# SCH_STM32__2024-11-28.net
KiCad netlist of a schematic drawn in EasyEDA
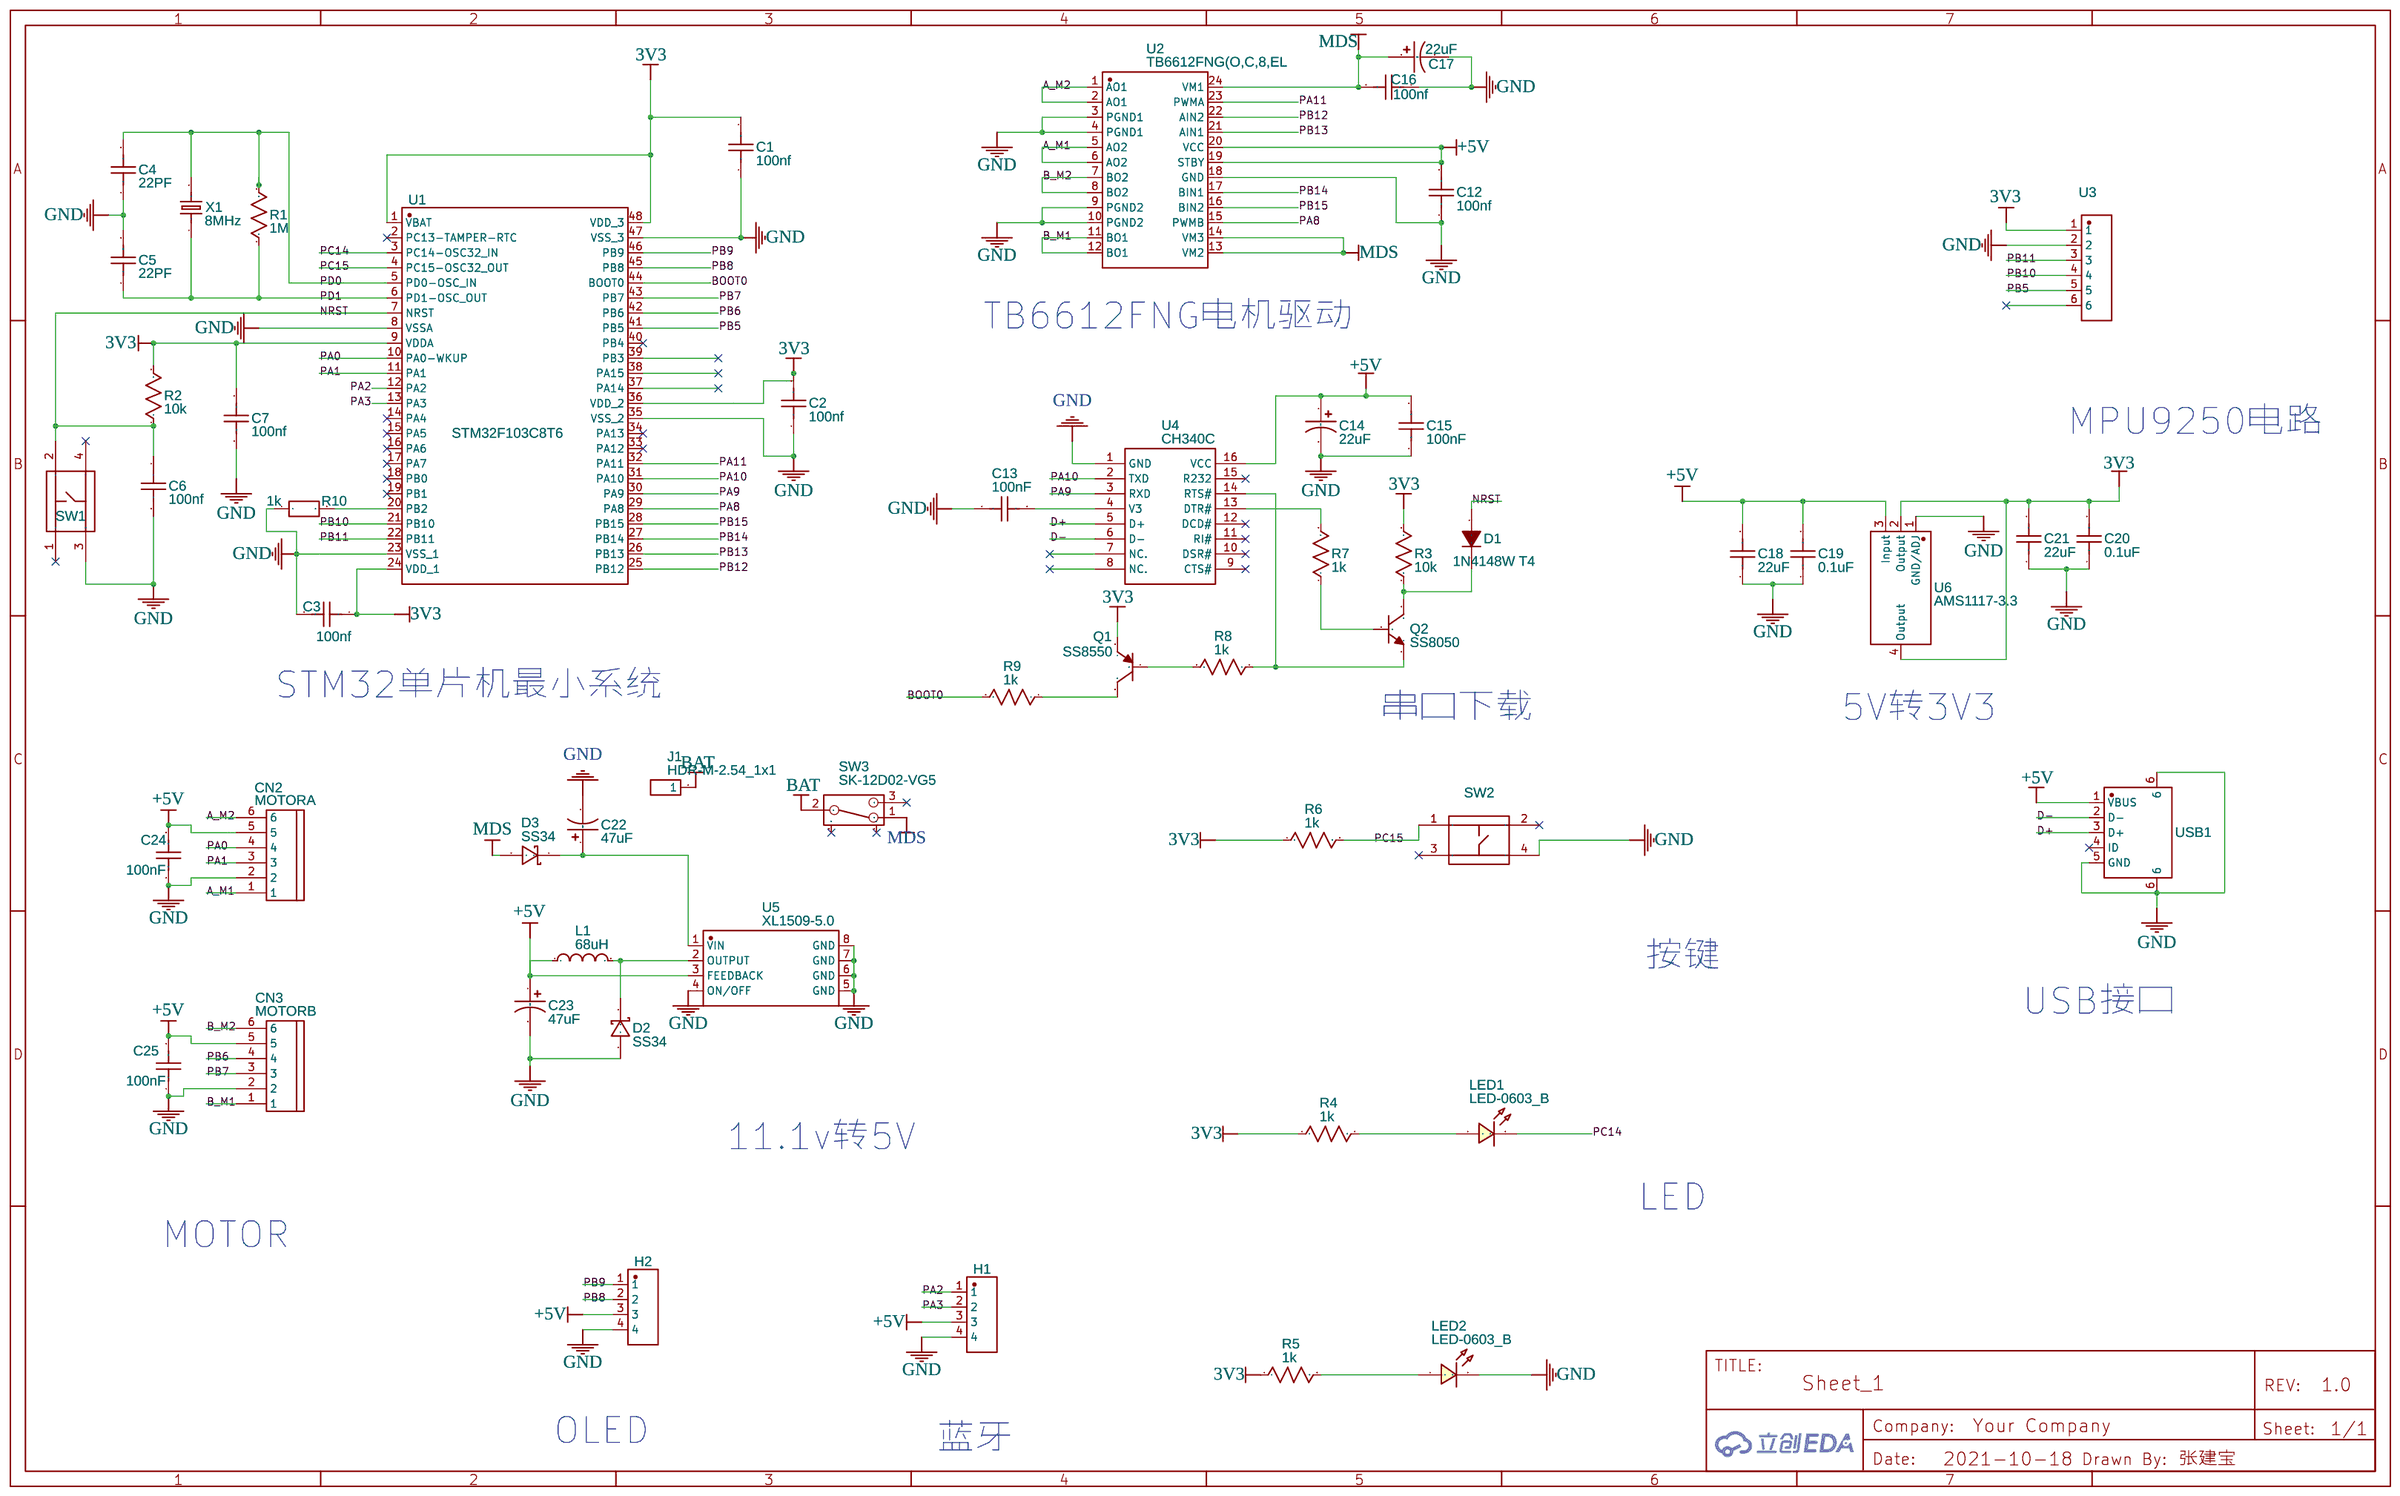
[diagram p0: schematic sheet]

(export (version "E")
  (design (tool "Eeschema 10.0.6"))
  (components
    (comp (ref "C1") (value "100nf") (libsource (lib "") (part "C_0805_US")))
    (comp (ref "C2") (value "100nf") (libsource (lib "") (part "C_0805_US")))
    (comp (ref "C3") (value "100nf") (libsource (lib "") (part "C_0805_US_1")))
    (comp (ref "C4") (value "22PF") (libsource (lib "") (part "C_0603_US")))
    (comp (ref "C5") (value "22PF") (libsource (lib "") (part "C_0603_US")))
    (comp (ref "C6") (value "100nf") (libsource (lib "") (part "C_0805_US_3")))
    (comp (ref "C7") (value "100nf") (libsource (lib "") (part "C_0805_US_3")))
    (comp (ref "C12") (value "100nf") (libsource (lib "") (part "C_0805_US")))
    (comp (ref "C13") (value "100nF") (libsource (lib "") (part "C_0805_US_2")))
    (comp (ref "C14") (value "22uF") (libsource (lib "") (part "C_Tan_SMD_A_US_3")))
    (comp (ref "C15") (value "100nF") (libsource (lib "") (part "C_0805_US")))
    (comp (ref "C16") (value "100nf") (libsource (lib "") (part "C_0805_US_1")))
    (comp (ref "C17") (value "22uF") (libsource (lib "") (part "C_Tan_SMD_A_US_2")))
    (comp (ref "C18") (value "22uF") (libsource (lib "") (part "C_0805_US")))
    (comp (ref "C19") (value "0.1uF") (libsource (lib "") (part "C_0805_US")))
    (comp (ref "C20") (value "0.1uF") (libsource (lib "") (part "C_0805_US")))
    (comp (ref "C21") (value "22uF") (libsource (lib "") (part "C_0805_US")))
    (comp (ref "C22") (value "47uF") (libsource (lib "") (part "C_Tan_SMD_A_US_1")))
    (comp (ref "C23") (value "47uF") (libsource (lib "") (part "C_Tan_SMD_A_US")))
    (comp (ref "C24") (value "100nF") (libsource (lib "") (part "C_0805_US")))
    (comp (ref "C25") (value "100nF") (libsource (lib "") (part "C_0805_US")))
    (comp (ref "CN2")
      (value "MOTORA")
      (fields (field (name "Manufacturer Part") "XH-6AW") (field (name "Manufacturer") "BOOMELE"))
      (libsource (lib "") (part "XH-6AW_C8876"))
    )
    (comp (ref "CN3")
      (value "MOTORB")
      (fields (field (name "Manufacturer Part") "XH-6AW") (field (name "Manufacturer") "BOOMELE"))
      (libsource (lib "") (part "XH-6AW_C8876"))
    )
    (comp (ref "D1")
      (value "1N4148W T4")
      (fields (field (name "Manufacturer") "CJ"))
      (libsource (lib "") (part "1N4148W T4"))
    )
    (comp (ref "D2")
      (value "SS34")
      (fields (field (name "Manufacturer") "High Diode"))
      (libsource (lib "") (part "SS34_C466502_1"))
    )
    (comp (ref "D3")
      (value "SS34")
      (fields (field (name "Manufacturer") "High Diode"))
      (libsource (lib "") (part "SS34_C466502"))
    )
    (comp (ref "H1")
      (value "2.54-1*4P母")
      (fields (field (name "Manufacturer") "BOOMELE(博穆精密)"))
      (libsource (lib "") (part "2.54-1*4P母"))
    )
    (comp (ref "H2")
      (value "2.54-1*4P母")
      (fields (field (name "Manufacturer") "BOOMELE(博穆精密)"))
      (libsource (lib "") (part "2.54-1*4P母"))
    )
    (comp (ref "J1") (value "HDR-M-2.54_1x1") (libsource (lib "") (part "HDR-M-2.54_1x1")))
    (comp (ref "L1")
      (value "68uH")
      (fields
        (field (name "Manufacturer Part") "SLH1207S680MTT")
        (field (name "Manufacturer") "Sunltech Tech")
      )
      (libsource (lib "") (part "SLH1207S680MTT"))
    )
    (comp (ref "LED1")
      (value "LED-0603_B")
      (fields
        (field (name "Manufacturer Part") "19-217/BHC-ZL1M2RY/3T")
        (field (name "Manufacturer") "EVERLIGHT(台湾亿光)")
      )
      (libsource (lib "") (part "LED-0603_B"))
    )
    (comp (ref "LED2")
      (value "LED-0603_B")
      (fields
        (field (name "Manufacturer Part") "19-217/BHC-ZL1M2RY/3T")
        (field (name "Manufacturer") "EVERLIGHT(台湾亿光)")
      )
      (libsource (lib "") (part "LED-0603_B"))
    )
    (comp (ref "Q1")
      (value "SS8550")
      (fields (field (name "Manufacturer") "晶导微电子"))
      (libsource (lib "") (part "SS8550_C2762207"))
    )
    (comp (ref "Q2")
      (value "SS8050")
      (fields (field (name "Manufacturer") "AnBon"))
      (libsource (lib "") (part "SS8050_C541705"))
    )
    (comp (ref "R1") (value "1M") (libsource (lib "") (part "R_0805_US_2")))
    (comp (ref "R2") (value "10k") (libsource (lib "") (part "R_0805_US_2")))
    (comp (ref "R3") (value "10k") (libsource (lib "") (part "R_0805_US_2")))
    (comp (ref "R4") (value "1k") (libsource (lib "") (part "R_0805_US")))
    (comp (ref "R5") (value "1k") (libsource (lib "") (part "R_0805_US")))
    (comp (ref "R6") (value "1k") (libsource (lib "") (part "R_0805_US")))
    (comp (ref "R7") (value "1k") (libsource (lib "") (part "R_0805_US_2")))
    (comp (ref "R8") (value "1k") (libsource (lib "") (part "R_0805_US_1")))
    (comp (ref "R9") (value "1k") (libsource (lib "") (part "R_0805_US_1")))
    (comp (ref "R10") (value "1k") (libsource (lib "") (part "R_0603_EU")))
    (comp (ref "SW1")
      (value "K2-1102DP-C4SW-04")
      (fields (field (name "Manufacturer") "HRO"))
      (libsource (lib "") (part "K2-1102DP-C4SW-04"))
    )
    (comp (ref "SW2")
      (value "K2-1102DP-C4SW-04")
      (fields (field (name "Manufacturer") "HRO"))
      (libsource (lib "") (part "K2-1102DP-C4SW-04_1"))
    )
    (comp (ref "SW3")
      (value "SK-12D02-VG5")
      (fields (field (name "Manufacturer") "Rectangular Connectors - Contacts"))
      (libsource (lib "") (part "SK-12D02-VG5"))
    )
    (comp (ref "U1")
      (value "STM32F103C8T6")
      (fields (field (name "Manufacturer") "STMicroelectronics"))
      (libsource (lib "") (part "STM32F103C8T6"))
    )
    (comp (ref "U2")
      (value "TB6612FNG(O,C,8,EL")
      (fields (field (name "Manufacturer") "TOSHIBA"))
      (libsource (lib "") (part "TB6612FNG(O,C,8,EL"))
    )
    (comp (ref "U3")
      (value "A2541HWV-6P_C2897443")
      (fields (field (name "Manufacturer Part") "A2541HWV-6P") (field (name "Manufacturer") "CJT(长江连接器)"))
      (libsource (lib "") (part "A2541HWV-6P_C2897443"))
    )
    (comp (ref "U4")
      (value "CH340C")
      (fields (field (name "Manufacturer") "WCH"))
      (libsource (lib "") (part "CH340C"))
    )
    (comp (ref "U5")
      (value "XL1509-5.0")
      (fields (field (name "Manufacturer") "UMW(友台半导体)"))
      (libsource (lib "") (part "XL1509-5.0_C2902368"))
    )
    (comp (ref "U6")
      (value "AMS1117-3.3")
      (fields (field (name "Manufacturer") "KEXIN"))
      (libsource (lib "") (part "AMS1117-3.3_C369933"))
    )
    (comp (ref "USB1")
      (value "U-M-M5DS-W-5_C2689963")
      (fields (field (name "Manufacturer Part") "U-M-M5DS-W-5") (field (name "Manufacturer") "韩国韩荣"))
      (libsource (lib "") (part "U-M-M5DS-W-5_C2689963"))
    )
    (comp (ref "X1")
      (value "8MHz")
      (fields
        (field (name "Manufacturer Part") "49S-8.000-20-20-20/A")
        (field (name "Manufacturer") "Suzhou Liming Elec")
      )
      (libsource (lib "") (part "49S-8.000-20-20-20/A"))
    )
  )
  (nets
    (net (code "1") (name "+5V") (class "Default")
      (node (ref "C12") (pin "2") (pinfunction "2_2") (pintype "unspecified"))
      (node (ref "C14") (pin "1") (pinfunction "1_1") (pintype "unspecified"))
      (node (ref "C15") (pin "2") (pinfunction "2_2") (pintype "unspecified"))
      (node (ref "C18") (pin "2") (pinfunction "2_2") (pintype "unspecified"))
      (node (ref "C19") (pin "2") (pinfunction "2_2") (pintype "unspecified"))
      (node (ref "C23") (pin "1") (pinfunction "1_1") (pintype "unspecified"))
      (node (ref "C24") (pin "2") (pinfunction "2_2") (pintype "unspecified"))
      (node (ref "C25") (pin "2") (pinfunction "2_2") (pintype "unspecified"))
      (node (ref "CN2") (pin "5") (pinfunction "5_5") (pintype "unspecified"))
      (node (ref "CN3") (pin "5") (pinfunction "5_5") (pintype "unspecified"))
      (node (ref "H1") (pin "3") (pinfunction "3_3") (pintype "unspecified"))
      (node (ref "H2") (pin "3") (pinfunction "3_3") (pintype "unspecified"))
      (node (ref "L1") (pin "1") (pinfunction "1_1") (pintype "unspecified"))
      (node (ref "U2") (pin "19") (pinfunction "STBY_19") (pintype "unspecified"))
      (node (ref "U2") (pin "20") (pinfunction "VCC_20") (pintype "unspecified"))
      (node (ref "U4") (pin "16") (pinfunction "VCC_16") (pintype "unspecified"))
      (node (ref "U5") (pin "3") (pinfunction "FEEDBACK_3") (pintype "unspecified"))
      (node (ref "U6") (pin "3") (pinfunction "Input_3") (pintype "unspecified"))
      (node (ref "USB1") (pin "1") (pinfunction "VBUS_1") (pintype "unspecified"))
    )
    (net (code "2") (name "/A_M1") (class "Default")
      (node (ref "CN2") (pin "1") (pinfunction "1_1") (pintype "unspecified"))
      (node (ref "U2") (pin "5") (pinfunction "AO2_5") (pintype "unspecified"))
      (node (ref "U2") (pin "6") (pinfunction "AO2_6") (pintype "unspecified"))
    )
    (net (code "3") (name "/A_M2") (class "Default")
      (node (ref "CN2") (pin "6") (pinfunction "6_6") (pintype "unspecified"))
      (node (ref "U2") (pin "1") (pinfunction "AO1_1") (pintype "unspecified"))
      (node (ref "U2") (pin "2") (pinfunction "AO1_2") (pintype "unspecified"))
    )
    (net (code "4") (name "/BOOT0") (class "Default")
      (node (ref "R9") (pin "2") (pinfunction "2_2") (pintype "unspecified"))
      (node (ref "U1") (pin "44") (pinfunction "BOOT0_44") (pintype "unspecified"))
    )
    (net (code "5") (name "/B_M1") (class "Default")
      (node (ref "CN3") (pin "1") (pinfunction "1_1") (pintype "unspecified"))
      (node (ref "U2") (pin "11") (pinfunction "BO1_11") (pintype "unspecified"))
      (node (ref "U2") (pin "12") (pinfunction "BO1_12") (pintype "unspecified"))
    )
    (net (code "6") (name "/B_M2") (class "Default")
      (node (ref "CN3") (pin "6") (pinfunction "6_6") (pintype "unspecified"))
      (node (ref "U2") (pin "7") (pinfunction "BO2_7") (pintype "unspecified"))
      (node (ref "U2") (pin "8") (pinfunction "BO2_8") (pintype "unspecified"))
    )
    (net (code "7") (name "/D+") (class "Default")
      (node (ref "U4") (pin "5") (pinfunction "D+_5") (pintype "unspecified"))
      (node (ref "USB1") (pin "3") (pinfunction "D+_3") (pintype "unspecified"))
    )
    (net (code "8") (name "/D-") (class "Default")
      (node (ref "U4") (pin "6") (pinfunction "D-_6") (pintype "unspecified"))
      (node (ref "USB1") (pin "2") (pinfunction "D-_2") (pintype "unspecified"))
    )
    (net (code "9") (name "/NRST") (class "Default")
      (node (ref "C6") (pin "1") (pinfunction "1_1") (pintype "unspecified"))
      (node (ref "D1") (pin "2") (pinfunction "A_2") (pintype "unspecified"))
      (node (ref "R2") (pin "1") (pinfunction "1_1") (pintype "unspecified"))
      (node (ref "SW1") (pin "2") (pinfunction "2_2") (pintype "unspecified"))
      (node (ref "U1") (pin "7") (pinfunction "NRST_7") (pintype "unspecified"))
    )
    (net (code "10") (name "/PA0") (class "Default")
      (node (ref "CN2") (pin "4") (pinfunction "4_4") (pintype "unspecified"))
      (node (ref "U1") (pin "10") (pinfunction "PA0-WKUP_10") (pintype "unspecified"))
    )
    (net (code "11") (name "/PA1") (class "Default")
      (node (ref "CN2") (pin "3") (pinfunction "3_3") (pintype "unspecified"))
      (node (ref "U1") (pin "11") (pinfunction "PA1_11") (pintype "unspecified"))
    )
    (net (code "12") (name "/PA2") (class "Default")
      (node (ref "H1") (pin "1") (pinfunction "1_1") (pintype "unspecified"))
      (node (ref "U1") (pin "12") (pinfunction "PA2_12") (pintype "unspecified"))
    )
    (net (code "13") (name "/PA3") (class "Default")
      (node (ref "H1") (pin "2") (pinfunction "2_2") (pintype "unspecified"))
      (node (ref "U1") (pin "13") (pinfunction "PA3_13") (pintype "unspecified"))
    )
    (net (code "14") (name "/PA8") (class "Default")
      (node (ref "U1") (pin "29") (pinfunction "PA8_29") (pintype "unspecified"))
      (node (ref "U2") (pin "15") (pinfunction "PWMB_15") (pintype "unspecified"))
    )
    (net (code "15") (name "/PA9") (class "Default")
      (node (ref "U1") (pin "30") (pinfunction "PA9_30") (pintype "unspecified"))
      (node (ref "U4") (pin "3") (pinfunction "RXD_3") (pintype "unspecified"))
    )
    (net (code "16") (name "/PA10") (class "Default")
      (node (ref "U1") (pin "31") (pinfunction "PA10_31") (pintype "unspecified"))
      (node (ref "U4") (pin "2") (pinfunction "TXD_2") (pintype "unspecified"))
    )
    (net (code "17") (name "/PA11") (class "Default")
      (node (ref "U1") (pin "32") (pinfunction "PA11_32") (pintype "unspecified"))
      (node (ref "U2") (pin "23") (pinfunction "PWMA_23") (pintype "unspecified"))
    )
    (net (code "18") (name "/PB5") (class "Default")
      (node (ref "U1") (pin "41") (pinfunction "PB5_41") (pintype "unspecified"))
      (node (ref "U3") (pin "5") (pinfunction "5_5") (pintype "unspecified"))
    )
    (net (code "19") (name "/PB6") (class "Default")
      (node (ref "CN3") (pin "4") (pinfunction "4_4") (pintype "unspecified"))
      (node (ref "U1") (pin "42") (pinfunction "PB6_42") (pintype "unspecified"))
    )
    (net (code "20") (name "/PB7") (class "Default")
      (node (ref "CN3") (pin "3") (pinfunction "3_3") (pintype "unspecified"))
      (node (ref "U1") (pin "43") (pinfunction "PB7_43") (pintype "unspecified"))
    )
    (net (code "21") (name "/PB8") (class "Default")
      (node (ref "H2") (pin "2") (pinfunction "2_2") (pintype "unspecified"))
      (node (ref "U1") (pin "45") (pinfunction "PB8_45") (pintype "unspecified"))
    )
    (net (code "22") (name "/PB9") (class "Default")
      (node (ref "H2") (pin "1") (pinfunction "1_1") (pintype "unspecified"))
      (node (ref "U1") (pin "46") (pinfunction "PB9_46") (pintype "unspecified"))
    )
    (net (code "23") (name "/PB10") (class "Default")
      (node (ref "U1") (pin "21") (pinfunction "PB10_21") (pintype "unspecified"))
      (node (ref "U3") (pin "4") (pinfunction "4_4") (pintype "unspecified"))
    )
    (net (code "24") (name "/PB11") (class "Default")
      (node (ref "U1") (pin "22") (pinfunction "PB11_22") (pintype "unspecified"))
      (node (ref "U3") (pin "3") (pinfunction "3_3") (pintype "unspecified"))
    )
    (net (code "25") (name "/PB12") (class "Default")
      (node (ref "U1") (pin "25") (pinfunction "PB12_25") (pintype "unspecified"))
      (node (ref "U2") (pin "22") (pinfunction "AIN2_22") (pintype "unspecified"))
    )
    (net (code "26") (name "/PB13") (class "Default")
      (node (ref "U1") (pin "26") (pinfunction "PB13_26") (pintype "unspecified"))
      (node (ref "U2") (pin "21") (pinfunction "AIN1_21") (pintype "unspecified"))
    )
    (net (code "27") (name "/PB14") (class "Default")
      (node (ref "U1") (pin "27") (pinfunction "PB14_27") (pintype "unspecified"))
      (node (ref "U2") (pin "17") (pinfunction "BIN1_17") (pintype "unspecified"))
    )
    (net (code "28") (name "/PB15") (class "Default")
      (node (ref "U1") (pin "28") (pinfunction "PB15_28") (pintype "unspecified"))
      (node (ref "U2") (pin "16") (pinfunction "BIN2_16") (pintype "unspecified"))
    )
    (net (code "29") (name "/PC14") (class "Default")
      (node (ref "LED1") (pin "2") (pinfunction "2_2") (pintype "unspecified"))
      (node (ref "U1") (pin "3") (pinfunction "PC14-OSC32_IN_3") (pintype "unspecified"))
    )
    (net (code "30") (name "/PC15") (class "Default")
      (node (ref "R6") (pin "2") (pinfunction "2_2") (pintype "unspecified"))
      (node (ref "SW2") (pin "1") (pinfunction "1_1") (pintype "unspecified"))
      (node (ref "U1") (pin "4") (pinfunction "PC15-OSC32_OUT_4") (pintype "unspecified"))
    )
    (net (code "31") (name "/PD0") (class "Default")
      (node (ref "C4") (pin "2") (pinfunction "2_2") (pintype "unspecified"))
      (node (ref "R1") (pin "2") (pinfunction "2_2") (pintype "unspecified"))
      (node (ref "U1") (pin "5") (pinfunction "PD0-OSC_IN_5") (pintype "unspecified"))
      (node (ref "X1") (pin "2") (pinfunction "2_2") (pintype "unspecified"))
    )
    (net (code "32") (name "/PD1") (class "Default")
      (node (ref "C5") (pin "1") (pinfunction "1_1") (pintype "unspecified"))
      (node (ref "R1") (pin "1") (pinfunction "1_1") (pintype "unspecified"))
      (node (ref "U1") (pin "6") (pinfunction "PD1-OSC_OUT_6") (pintype "unspecified"))
      (node (ref "X1") (pin "1") (pinfunction "1_1") (pintype "unspecified"))
    )
    (net (code "33") (name "3V3") (class "Default")
      (node (ref "C1") (pin "2") (pinfunction "2_2") (pintype "unspecified"))
      (node (ref "C2") (pin "2") (pinfunction "2_2") (pintype "unspecified"))
      (node (ref "C20") (pin "2") (pinfunction "2_2") (pintype "unspecified"))
      (node (ref "C21") (pin "2") (pinfunction "2_2") (pintype "unspecified"))
      (node (ref "C3") (pin "1") (pinfunction "1_1") (pintype "unspecified"))
      (node (ref "C7") (pin "1") (pinfunction "1_1") (pintype "unspecified"))
      (node (ref "Q1") (pin "2") (pinfunction "E_2") (pintype "unspecified"))
      (node (ref "R2") (pin "2") (pinfunction "2_2") (pintype "unspecified"))
      (node (ref "R3") (pin "2") (pinfunction "2_2") (pintype "unspecified"))
      (node (ref "R4") (pin "1") (pinfunction "1_1") (pintype "unspecified"))
      (node (ref "R5") (pin "1") (pinfunction "1_1") (pintype "unspecified"))
      (node (ref "R6") (pin "1") (pinfunction "1_1") (pintype "unspecified"))
      (node (ref "U1") (pin "1") (pinfunction "VBAT_1") (pintype "unspecified"))
      (node (ref "U1") (pin "24") (pinfunction "VDD_1_24") (pintype "unspecified"))
      (node (ref "U1") (pin "36") (pinfunction "VDD_2_36") (pintype "unspecified"))
      (node (ref "U1") (pin "48") (pinfunction "VDD_3_48") (pintype "unspecified"))
      (node (ref "U1") (pin "9") (pinfunction "VDDA_9") (pintype "unspecified"))
      (node (ref "U3") (pin "1") (pinfunction "1_1") (pintype "unspecified"))
      (node (ref "U6") (pin "2") (pinfunction "Output_2") (pintype "unspecified"))
      (node (ref "U6") (pin "4") (pinfunction "Output_4") (pintype "unspecified"))
    )
    (net (code "34") (name "BAT") (class "Default")
      (node (ref "J1") (pin "1") (pinfunction "1_1") (pintype "input"))
      (node (ref "SW3") (pin "2") (pinfunction "2_2") (pintype "unspecified"))
    )
    (net (code "35") (name "GND") (class "Default")
      (node (ref "C1") (pin "1") (pinfunction "1_1") (pintype "unspecified"))
      (node (ref "C12") (pin "1") (pinfunction "1_1") (pintype "unspecified"))
      (node (ref "C13") (pin "1") (pinfunction "1_1") (pintype "unspecified"))
      (node (ref "C14") (pin "2") (pinfunction "2_2") (pintype "unspecified"))
      (node (ref "C15") (pin "1") (pinfunction "1_1") (pintype "unspecified"))
      (node (ref "C16") (pin "1") (pinfunction "1_1") (pintype "unspecified"))
      (node (ref "C17") (pin "2") (pinfunction "2_2") (pintype "unspecified"))
      (node (ref "C18") (pin "1") (pinfunction "1_1") (pintype "unspecified"))
      (node (ref "C19") (pin "1") (pinfunction "1_1") (pintype "unspecified"))
      (node (ref "C2") (pin "1") (pinfunction "1_1") (pintype "unspecified"))
      (node (ref "C20") (pin "1") (pinfunction "1_1") (pintype "unspecified"))
      (node (ref "C21") (pin "1") (pinfunction "1_1") (pintype "unspecified"))
      (node (ref "C22") (pin "2") (pinfunction "2_2") (pintype "unspecified"))
      (node (ref "C23") (pin "2") (pinfunction "2_2") (pintype "unspecified"))
      (node (ref "C24") (pin "1") (pinfunction "1_1") (pintype "unspecified"))
      (node (ref "C25") (pin "1") (pinfunction "1_1") (pintype "unspecified"))
      (node (ref "C3") (pin "2") (pinfunction "2_2") (pintype "unspecified"))
      (node (ref "C4") (pin "1") (pinfunction "1_1") (pintype "unspecified"))
      (node (ref "C5") (pin "2") (pinfunction "2_2") (pintype "unspecified"))
      (node (ref "C6") (pin "2") (pinfunction "2_2") (pintype "unspecified"))
      (node (ref "C7") (pin "2") (pinfunction "2_2") (pintype "unspecified"))
      (node (ref "CN2") (pin "2") (pinfunction "2_2") (pintype "unspecified"))
      (node (ref "CN3") (pin "2") (pinfunction "2_2") (pintype "unspecified"))
      (node (ref "D2") (pin "2") (pinfunction "2_2") (pintype "unspecified"))
      (node (ref "H1") (pin "4") (pinfunction "4_4") (pintype "unspecified"))
      (node (ref "H2") (pin "4") (pinfunction "4_4") (pintype "unspecified"))
      (node (ref "LED2") (pin "2") (pinfunction "2_2") (pintype "unspecified"))
      (node (ref "R10") (pin "1") (pinfunction "1_1") (pintype "unspecified"))
      (node (ref "SW1") (pin "3") (pinfunction "3_3") (pintype "unspecified"))
      (node (ref "SW2") (pin "4") (pinfunction "4_4") (pintype "unspecified"))
      (node (ref "U1") (pin "23") (pinfunction "VSS_1_23") (pintype "unspecified"))
      (node (ref "U1") (pin "35") (pinfunction "VSS_2_35") (pintype "unspecified"))
      (node (ref "U1") (pin "47") (pinfunction "VSS_3_47") (pintype "unspecified"))
      (node (ref "U1") (pin "8") (pinfunction "VSSA_8") (pintype "unspecified"))
      (node (ref "U2") (pin "10") (pinfunction "PGND2_10") (pintype "unspecified"))
      (node (ref "U2") (pin "18") (pinfunction "GND_18") (pintype "unspecified"))
      (node (ref "U2") (pin "3") (pinfunction "PGND1_3") (pintype "unspecified"))
      (node (ref "U2") (pin "4") (pinfunction "PGND1_4") (pintype "unspecified"))
      (node (ref "U2") (pin "9") (pinfunction "PGND2_9") (pintype "unspecified"))
      (node (ref "U3") (pin "2") (pinfunction "2_2") (pintype "unspecified"))
      (node (ref "U4") (pin "1") (pinfunction "GND_1") (pintype "unspecified"))
      (node (ref "U5") (pin "4") (pinfunction "ON/OFF_4") (pintype "unspecified"))
      (node (ref "U5") (pin "5") (pinfunction "GND_5") (pintype "unspecified"))
      (node (ref "U5") (pin "6") (pinfunction "GND_6") (pintype "unspecified"))
      (node (ref "U5") (pin "7") (pinfunction "GND_7") (pintype "unspecified"))
      (node (ref "U5") (pin "8") (pinfunction "GND_8") (pintype "unspecified"))
      (node (ref "U6") (pin "1") (pinfunction "GND/ADJ_1") (pintype "unspecified"))
      (node (ref "USB1") (pin "5") (pinfunction "GND_5") (pintype "unspecified"))
      (node (ref "USB1") (pin "6") (pinfunction "6_6") (pintype "unspecified"))
    )
    (net (code "36") (name "MDS") (class "Default")
      (node (ref "C16") (pin "2") (pinfunction "2_2") (pintype "unspecified"))
      (node (ref "C17") (pin "1") (pinfunction "1_1") (pintype "unspecified"))
      (node (ref "D3") (pin "2") (pinfunction "2_2") (pintype "unspecified"))
      (node (ref "SW3") (pin "1") (pinfunction "1_1") (pintype "unspecified"))
      (node (ref "U2") (pin "13") (pinfunction "VM2_13") (pintype "unspecified"))
      (node (ref "U2") (pin "14") (pinfunction "VM3_14") (pintype "unspecified"))
      (node (ref "U2") (pin "24") (pinfunction "VM1_24") (pintype "unspecified"))
    )
    (net (code "37") (name "Net-(D1-K)") (class "Default")
      (node (ref "D1") (pin "1") (pinfunction "K_1") (pintype "unspecified"))
      (node (ref "Q2") (pin "3") (pinfunction "C_3") (pintype "unspecified"))
      (node (ref "R3") (pin "1") (pinfunction "1_1") (pintype "unspecified"))
    )
    (net (code "38") (name "Net-(LED1-Pad1)") (class "Default")
      (node (ref "LED1") (pin "1") (pinfunction "1_1") (pintype "unspecified"))
      (node (ref "R4") (pin "2") (pinfunction "2_2") (pintype "unspecified"))
    )
    (net (code "39") (name "Net-(LED2-Pad1)") (class "Default")
      (node (ref "LED2") (pin "1") (pinfunction "1_1") (pintype "unspecified"))
      (node (ref "R5") (pin "2") (pinfunction "2_2") (pintype "unspecified"))
    )
    (net (code "40") (name "Net-(Q1-B)") (class "Default")
      (node (ref "Q1") (pin "1") (pinfunction "B_1") (pintype "unspecified"))
      (node (ref "R8") (pin "2") (pinfunction "2_2") (pintype "unspecified"))
    )
    (net (code "41") (name "Net-(Q1-C)") (class "Default")
      (node (ref "Q1") (pin "3") (pinfunction "C_3") (pintype "unspecified"))
      (node (ref "R9") (pin "1") (pinfunction "1_1") (pintype "unspecified"))
    )
    (net (code "42") (name "Net-(Q2-B)") (class "Default")
      (node (ref "Q2") (pin "1") (pinfunction "B_1") (pintype "unspecified"))
      (node (ref "R7") (pin "1") (pinfunction "1_1") (pintype "unspecified"))
    )
    (net (code "43") (name "Net-(Q2-E)") (class "Default")
      (node (ref "Q2") (pin "2") (pinfunction "E_2") (pintype "unspecified"))
      (node (ref "R8") (pin "1") (pinfunction "1_1") (pintype "unspecified"))
      (node (ref "U4") (pin "14") (pinfunction "RTS#_14") (pintype "unspecified"))
    )
    (net (code "44") (name "Net-(U1-PB2)") (class "Default")
      (node (ref "R10") (pin "2") (pinfunction "2_2") (pintype "unspecified"))
      (node (ref "U1") (pin "20") (pinfunction "PB2_20") (pintype "unspecified"))
    )
    (net (code "45") (name "Net-(U4-DTR#)") (class "Default")
      (node (ref "R7") (pin "2") (pinfunction "2_2") (pintype "unspecified"))
      (node (ref "U4") (pin "13") (pinfunction "DTR#_13") (pintype "unspecified"))
    )
    (net (code "46") (name "Net-(U4-V3)") (class "Default")
      (node (ref "C13") (pin "2") (pinfunction "2_2") (pintype "unspecified"))
      (node (ref "U4") (pin "4") (pinfunction "V3_4") (pintype "unspecified"))
    )
    (net (code "47") (name "Net-(U5-OUTPUT)") (class "Default")
      (node (ref "D2") (pin "1") (pinfunction "1_1") (pintype "unspecified"))
      (node (ref "L1") (pin "2") (pinfunction "2_2") (pintype "unspecified"))
      (node (ref "U5") (pin "2") (pinfunction "OUTPUT_2") (pintype "unspecified"))
    )
    (net (code "48") (name "Net-(U5-VIN)") (class "Default")
      (node (ref "C22") (pin "1") (pinfunction "1_1") (pintype "unspecified"))
      (node (ref "D3") (pin "1") (pinfunction "1_1") (pintype "unspecified"))
      (node (ref "U5") (pin "1") (pinfunction "VIN_1") (pintype "unspecified"))
    )
    (net (code "49") (name "unconnected-(SW1-Pad1)") (class "Default")
      (node (ref "SW1") (pin "1") (pinfunction "1_1") (pintype "unspecified+no_connect"))
    )
    (net (code "50") (name "unconnected-(SW1-Pad4)") (class "Default")
      (node (ref "SW1") (pin "4") (pinfunction "4_4") (pintype "unspecified+no_connect"))
    )
    (net (code "51") (name "unconnected-(SW2-Pad2)") (class "Default")
      (node (ref "SW2") (pin "2") (pinfunction "2_2") (pintype "unspecified+no_connect"))
    )
    (net (code "52") (name "unconnected-(SW2-Pad3)") (class "Default")
      (node (ref "SW2") (pin "3") (pinfunction "3_3") (pintype "unspecified+no_connect"))
    )
    (net (code "53") (name "unconnected-(SW3-Pad3)") (class "Default")
      (node (ref "SW3") (pin "3") (pinfunction "3_3") (pintype "unspecified+no_connect"))
    )
    (net (code "54") (name "unconnected-(SW3-Pad4)") (class "Default")
      (node (ref "SW3") (pin "4") (pinfunction "4_4") (pintype "unspecified+no_connect"))
    )
    (net (code "55") (name "unconnected-(SW3-Pad5)") (class "Default")
      (node (ref "SW3") (pin "5") (pinfunction "5_5") (pintype "unspecified+no_connect"))
    )
    (net (code "56") (name "unconnected-(U1-PA4-Pad14)") (class "Default")
      (node (ref "U1") (pin "14") (pinfunction "PA4_14") (pintype "unspecified+no_connect"))
    )
    (net (code "57") (name "unconnected-(U1-PA5-Pad15)") (class "Default")
      (node (ref "U1") (pin "15") (pinfunction "PA5_15") (pintype "unspecified+no_connect"))
    )
    (net (code "58") (name "unconnected-(U1-PA6-Pad16)") (class "Default")
      (node (ref "U1") (pin "16") (pinfunction "PA6_16") (pintype "unspecified+no_connect"))
    )
    (net (code "59") (name "unconnected-(U1-PA7-Pad17)") (class "Default")
      (node (ref "U1") (pin "17") (pinfunction "PA7_17") (pintype "unspecified+no_connect"))
    )
    (net (code "60") (name "unconnected-(U1-PA12-Pad33)") (class "Default")
      (node (ref "U1") (pin "33") (pinfunction "PA12_33") (pintype "unspecified+no_connect"))
    )
    (net (code "61") (name "unconnected-(U1-PA13-Pad34)") (class "Default")
      (node (ref "U1") (pin "34") (pinfunction "PA13_34") (pintype "unspecified+no_connect"))
    )
    (net (code "62") (name "unconnected-(U1-PA14-Pad37)") (class "Default")
      (node (ref "U1") (pin "37") (pinfunction "PA14_37") (pintype "unspecified+no_connect"))
    )
    (net (code "63") (name "unconnected-(U1-PA15-Pad38)") (class "Default")
      (node (ref "U1") (pin "38") (pinfunction "PA15_38") (pintype "unspecified+no_connect"))
    )
    (net (code "64") (name "unconnected-(U1-PB0-Pad18)") (class "Default")
      (node (ref "U1") (pin "18") (pinfunction "PB0_18") (pintype "unspecified+no_connect"))
    )
    (net (code "65") (name "unconnected-(U1-PB1-Pad19)") (class "Default")
      (node (ref "U1") (pin "19") (pinfunction "PB1_19") (pintype "unspecified+no_connect"))
    )
    (net (code "66") (name "unconnected-(U1-PB3-Pad39)") (class "Default")
      (node (ref "U1") (pin "39") (pinfunction "PB3_39") (pintype "unspecified+no_connect"))
    )
    (net (code "67") (name "unconnected-(U1-PB4-Pad40)") (class "Default")
      (node (ref "U1") (pin "40") (pinfunction "PB4_40") (pintype "unspecified+no_connect"))
    )
    (net (code "68") (name "unconnected-(U1-PC13-TAMPER-RTC-Pad2)") (class "Default")
      (node (ref "U1") (pin "2") (pinfunction "PC13-TAMPER-RTC_2") (pintype "unspecified+no_connect"))
    )
    (net (code "69") (name "unconnected-(U3-Pad6)") (class "Default")
      (node (ref "U3") (pin "6") (pinfunction "6_6") (pintype "unspecified+no_connect"))
    )
    (net (code "70") (name "unconnected-(U4-CTS#-Pad9)") (class "Default")
      (node (ref "U4") (pin "9") (pinfunction "CTS#_9") (pintype "unspecified+no_connect"))
    )
    (net (code "71") (name "unconnected-(U4-DCD#-Pad12)") (class "Default")
      (node (ref "U4") (pin "12") (pinfunction "DCD#_12") (pintype "unspecified+no_connect"))
    )
    (net (code "72") (name "unconnected-(U4-DSR#-Pad10)") (class "Default")
      (node (ref "U4") (pin "10") (pinfunction "DSR#_10") (pintype "unspecified+no_connect"))
    )
    (net (code "73") (name "unconnected-(U4-NC.-Pad7)") (class "Default")
      (node (ref "U4") (pin "7") (pinfunction "NC._7") (pintype "unspecified+no_connect"))
    )
    (net (code "74") (name "unconnected-(U4-NC.-Pad8)") (class "Default")
      (node (ref "U4") (pin "8") (pinfunction "NC._8") (pintype "unspecified+no_connect"))
    )
    (net (code "75") (name "unconnected-(U4-R232-Pad15)") (class "Default")
      (node (ref "U4") (pin "15") (pinfunction "R232_15") (pintype "unspecified+no_connect"))
    )
    (net (code "76") (name "unconnected-(U4-RI#-Pad11)") (class "Default")
      (node (ref "U4") (pin "11") (pinfunction "RI#_11") (pintype "unspecified+no_connect"))
    )
    (net (code "77") (name "unconnected-(USB1-ID-Pad4)") (class "Default")
      (node (ref "USB1") (pin "4") (pinfunction "ID_4") (pintype "unspecified+no_connect"))
    )
  )
)
